# Emergancy.net
KiCad netlist of a schematic drawn in Altium Designer
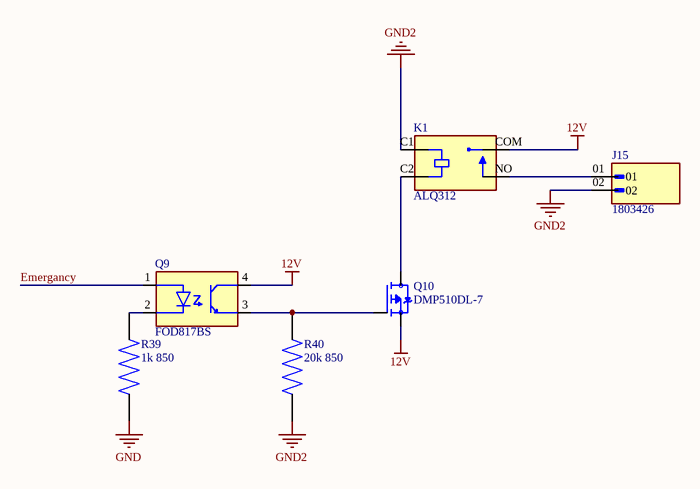
[diagram p0: Emergancy.SchDoc]

(export (version "E")
  (design (tool "Eeschema 10.0.6"))
  (components
    (comp (ref "J15")
      (value "1803426")
      (footprint "PHOENIX_1803426")
      (description "Pluggable Header 3.81mm 16AWG 160V 8A 2 Position COMBICON MCV Series ¦ Phoenix Contact 1803426")
      (fields (field (name "MF") "Phoenix Contact"))
      (libsource (lib "iee_altium") (part "1803426"))
    )
    (comp (ref "K1")
      (value "ALQ312")
      (footprint "RELAY_ALQ312")
      (description "General Purpose Relay SPST-NO (1 Form A) 12VDC Coil Through Hole")
      (fields (field (name "MF") "Panasonic Electric"))
      (libsource (lib "iee_altium") (part "ALQ312"))
    )
    (comp (ref "Q9")
      (value "FOD817BS")
      (footprint "SOIC254P1016X385-4N")
      (description "Transistor Output Optocouplers Opto Phototransistor Output SM-DIP4")
      (fields (field (name "MF") "ON Semiconductor"))
      (libsource (lib "iee_altium") (part "FOD817BS"))
    )
    (comp (ref "Q10")
      (value "DMP510DL-7")
      (footprint "SOT91P240X110-3N - duplicate")
      (libsource (lib "iee_altium") (part "DMP510DL-7"))
    )
    (comp (ref "R39") (value "1k 850") (footprint "10k 850") (libsource (lib "iee_altium") (part "10k 850")))
    (comp (ref "R40") (value "20k 850") (footprint "10k 850") (libsource (lib "iee_altium") (part "10k 850")))
  )
  (nets
    (net (code "1") (name "/Emergancy") (class "Default")
      (node (ref "Q9") (pin "1") (pinfunction "ANODE_1") (pintype "passive"))
    )
    (net (code "2") (name "12V") (class "Default")
      (node (ref "K1") (pin "COM") (pinfunction "COM_COM") (pintype "passive"))
      (node (ref "Q10") (pin "2") (pinfunction "S_2") (pintype "passive"))
      (node (ref "Q9") (pin "4") (pinfunction "COLLECTOR_4") (pintype "passive"))
    )
    (net (code "3") (name "GND") (class "Default")
      (node (ref "R39") (pin "2") (pinfunction "2_2") (pintype "passive"))
    )
    (net (code "4") (name "GND2") (class "Default")
      (node (ref "J15") (pin "02") (pinfunction "02_02") (pintype "passive"))
      (node (ref "K1") (pin "C1") (pinfunction "COIL1_C1") (pintype "passive"))
      (node (ref "R40") (pin "2") (pinfunction "2_2") (pintype "passive"))
    )
    (net (code "5") (name "Net-(J15-Pad01)") (class "Default")
      (node (ref "J15") (pin "01") (pinfunction "01_01") (pintype "passive"))
      (node (ref "K1") (pin "NO") (pinfunction "NO_NO") (pintype "passive"))
    )
    (net (code "6") (name "Net-(K1-COIL2)") (class "Default")
      (node (ref "K1") (pin "C2") (pinfunction "COIL2_C2") (pintype "passive"))
      (node (ref "Q10") (pin "3") (pinfunction "D_3") (pintype "passive"))
    )
    (net (code "7") (name "Net-(Q9-CATHODE)") (class "Default")
      (node (ref "Q9") (pin "2") (pinfunction "CATHODE_2") (pintype "passive"))
      (node (ref "R39") (pin "1") (pinfunction "1_1") (pintype "passive"))
    )
    (net (code "8") (name "Net-(Q10-G)") (class "Default")
      (node (ref "Q10") (pin "1") (pinfunction "G_1") (pintype "passive"))
      (node (ref "Q9") (pin "3") (pinfunction "EMITTER_3") (pintype "passive"))
      (node (ref "R40") (pin "1") (pinfunction "1_1") (pintype "passive"))
    )
  )
)
